# QuadDXL.net
KiCad netlist of a schematic drawn in EAGLE
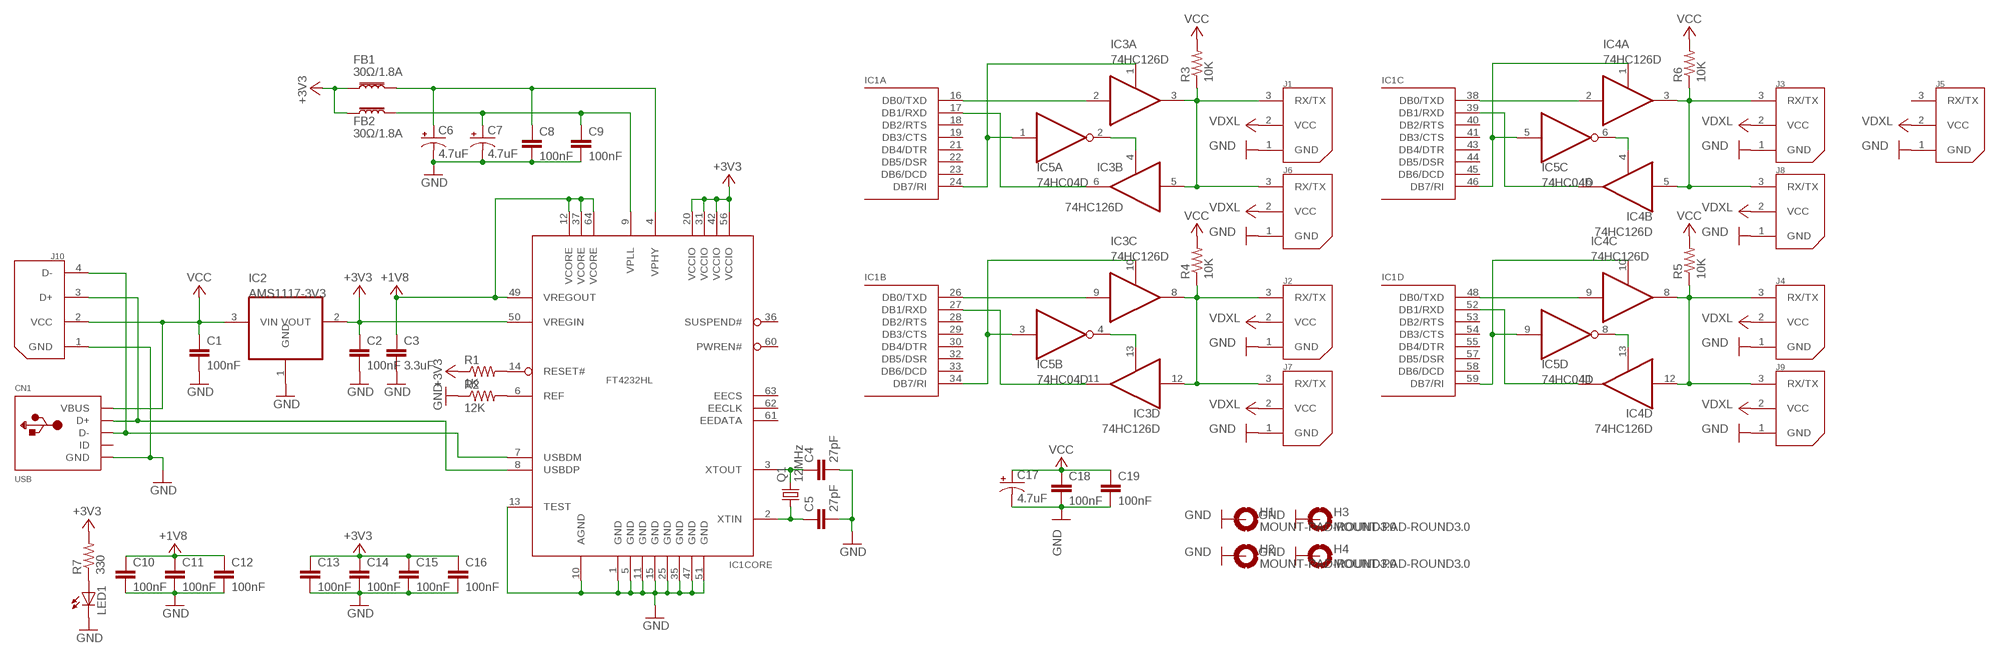
[diagram p0: schematic, sheet 1]

(export (version "E")
  (design (tool "Eeschema 10.0.6"))
  (components
    (comp (ref "C1")
      (value "100nF")
      (footprint "eagle-import:C0603K")
      (libsource (lib "eagle-import") (part "C-EUC0603K"))
    )
    (comp (ref "C2")
      (value "100nF")
      (footprint "eagle-import:C0603K")
      (libsource (lib "eagle-import") (part "C-EUC0603K"))
    )
    (comp (ref "C3")
      (value "3.3uF")
      (footprint "eagle-import:C0603K")
      (libsource (lib "eagle-import") (part "C-EUC0603K"))
    )
    (comp (ref "C4")
      (value "27pF")
      (footprint "eagle-import:C0603K")
      (libsource (lib "eagle-import") (part "C-EUC0603K"))
    )
    (comp (ref "C5")
      (value "27pF")
      (footprint "eagle-import:C0603K")
      (libsource (lib "eagle-import") (part "C-EUC0603K"))
    )
    (comp (ref "C6")
      (value "4.7uF")
      (footprint "eagle-import:CT3216")
      (libsource (lib "eagle-import") (part "CPOL-USCT3216"))
    )
    (comp (ref "C7")
      (value "4.7uF")
      (footprint "eagle-import:CT3216")
      (libsource (lib "eagle-import") (part "CPOL-USCT3216"))
    )
    (comp (ref "C8")
      (value "100nF")
      (footprint "eagle-import:C0603K")
      (libsource (lib "eagle-import") (part "C-EUC0603K"))
    )
    (comp (ref "C9")
      (value "100nF")
      (footprint "eagle-import:C0603K")
      (libsource (lib "eagle-import") (part "C-EUC0603K"))
    )
    (comp (ref "C10")
      (value "100nF")
      (footprint "eagle-import:C0603K")
      (libsource (lib "eagle-import") (part "C-EUC0603K"))
    )
    (comp (ref "C11")
      (value "100nF")
      (footprint "eagle-import:C0603K")
      (libsource (lib "eagle-import") (part "C-EUC0603K"))
    )
    (comp (ref "C12")
      (value "100nF")
      (footprint "eagle-import:C0603K")
      (libsource (lib "eagle-import") (part "C-EUC0603K"))
    )
    (comp (ref "C13")
      (value "100nF")
      (footprint "eagle-import:C0603K")
      (libsource (lib "eagle-import") (part "C-EUC0603K"))
    )
    (comp (ref "C14")
      (value "100nF")
      (footprint "eagle-import:C0603K")
      (libsource (lib "eagle-import") (part "C-EUC0603K"))
    )
    (comp (ref "C15")
      (value "100nF")
      (footprint "eagle-import:C0603K")
      (libsource (lib "eagle-import") (part "C-EUC0603K"))
    )
    (comp (ref "C16")
      (value "100nF")
      (footprint "eagle-import:C0603K")
      (libsource (lib "eagle-import") (part "C-EUC0603K"))
    )
    (comp (ref "C17")
      (value "4.7uF")
      (footprint "eagle-import:CT3216")
      (libsource (lib "eagle-import") (part "CPOL-USCT3216"))
    )
    (comp (ref "C18")
      (value "100nF")
      (footprint "eagle-import:C0603K")
      (libsource (lib "eagle-import") (part "C-EUC0603K"))
    )
    (comp (ref "C19")
      (value "100nF")
      (footprint "eagle-import:C0603K")
      (libsource (lib "eagle-import") (part "C-EUC0603K"))
    )
    (comp (ref "CN1")
      (value "USB")
      (footprint "eagle-import:USB-MINIB")
      (libsource (lib "eagle-import") (part "USBMINIB"))
    )
    (comp (ref "FB1")
      (value "30Ω/1.8A")
      (footprint "eagle-import:0603")
      (libsource (lib "eagle-import") (part "FERRITE_BEAD-0603"))
    )
    (comp (ref "FB2")
      (value "30Ω/1.8A")
      (footprint "eagle-import:0603")
      (libsource (lib "eagle-import") (part "FERRITE_BEAD-0603"))
    )
    (comp (ref "H1")
      (value "MOUNT-PAD-ROUND3.0")
      (footprint "eagle-import:3,0-PAD")
      (libsource (lib "eagle-import") (part "MOUNT-PAD-ROUND3.0"))
    )
    (comp (ref "H2")
      (value "MOUNT-PAD-ROUND3.0")
      (footprint "eagle-import:3,0-PAD")
      (libsource (lib "eagle-import") (part "MOUNT-PAD-ROUND3.0"))
    )
    (comp (ref "H3")
      (value "MOUNT-PAD-ROUND3.0")
      (footprint "eagle-import:3,0-PAD")
      (libsource (lib "eagle-import") (part "MOUNT-PAD-ROUND3.0"))
    )
    (comp (ref "H4")
      (value "MOUNT-PAD-ROUND3.0")
      (footprint "eagle-import:3,0-PAD")
      (libsource (lib "eagle-import") (part "MOUNT-PAD-ROUND3.0"))
    )
    (comp (ref "IC1")
      (value "FT4232HL")
      (footprint "eagle-import:LQFP64")
      (libsource (lib "eagle-import") (part "FT4232HL"))
    )
    (comp (ref "IC2")
      (value "AMS1117-3V3")
      (footprint "eagle-import:SOT223")
      (fields (field (name "MPN") "REG1117"))
      (libsource (lib "eagle-import") (part "REG1117"))
    )
    (comp (ref "IC3")
      (value "74HC126D")
      (footprint "eagle-import:SO14")
      (libsource (lib "eagle-import") (part "74126DHC"))
    )
    (comp (ref "IC4")
      (value "74HC126D")
      (footprint "eagle-import:SO14")
      (libsource (lib "eagle-import") (part "74126DHC"))
    )
    (comp (ref "IC5")
      (value "74HC04D")
      (footprint "eagle-import:SO14")
      (libsource (lib "eagle-import") (part "7404DHC"))
    )
    (comp (ref "J1")
      (value "22-03-5035")
      (footprint "eagle-import:5267-3")
      (libsource (lib "eagle-import") (part "22-03-5035"))
    )
    (comp (ref "J2")
      (value "22-03-5035")
      (footprint "eagle-import:5267-3")
      (libsource (lib "eagle-import") (part "22-03-5035"))
    )
    (comp (ref "J3")
      (value "22-03-5035")
      (footprint "eagle-import:5267-3")
      (libsource (lib "eagle-import") (part "22-03-5035"))
    )
    (comp (ref "J4")
      (value "22-03-5035")
      (footprint "eagle-import:5267-3")
      (libsource (lib "eagle-import") (part "22-03-5035"))
    )
    (comp (ref "J5")
      (value "DXL_POWER")
      (footprint "eagle-import:5267-3")
      (libsource (lib "eagle-import") (part "22-03-5035"))
    )
    (comp (ref "J6")
      (value "22-03-5035")
      (footprint "eagle-import:5267-3")
      (libsource (lib "eagle-import") (part "22-03-5035"))
    )
    (comp (ref "J7")
      (value "22-03-5035")
      (footprint "eagle-import:5267-3")
      (libsource (lib "eagle-import") (part "22-03-5035"))
    )
    (comp (ref "J8")
      (value "22-03-5035")
      (footprint "eagle-import:5267-3")
      (libsource (lib "eagle-import") (part "22-03-5035"))
    )
    (comp (ref "J9")
      (value "22-03-5035")
      (footprint "eagle-import:5267-3")
      (libsource (lib "eagle-import") (part "22-03-5035"))
    )
    (comp (ref "J10")
      (value "USB")
      (footprint "eagle-import:5267-4")
      (libsource (lib "eagle-import") (part "22-03-5045"))
    )
    (comp (ref "LED1")
      (value "LEDCHIP-LED0603")
      (footprint "eagle-import:CHIP-LED0603")
      (libsource (lib "eagle-import") (part "LEDCHIP-LED0603"))
    )
    (comp (ref "Q1")
      (value "12MHz")
      (footprint "eagle-import:HC49UP")
      (libsource (lib "eagle-import") (part "CRYSTALHC49UP"))
    )
    (comp (ref "R1")
      (value "1K")
      (footprint "eagle-import:R0603")
      (libsource (lib "eagle-import") (part "R-US_R0603"))
    )
    (comp (ref "R2")
      (value "12K")
      (footprint "eagle-import:R0603")
      (libsource (lib "eagle-import") (part "R-US_R0603"))
    )
    (comp (ref "R3")
      (value "10K")
      (footprint "eagle-import:R0603")
      (libsource (lib "eagle-import") (part "R-US_R0603"))
    )
    (comp (ref "R4")
      (value "10K")
      (footprint "eagle-import:R0603")
      (libsource (lib "eagle-import") (part "R-US_R0603"))
    )
    (comp (ref "R5")
      (value "10K")
      (footprint "eagle-import:R0603")
      (libsource (lib "eagle-import") (part "R-US_R0603"))
    )
    (comp (ref "R6")
      (value "10K")
      (footprint "eagle-import:R0603")
      (libsource (lib "eagle-import") (part "R-US_R0603"))
    )
    (comp (ref "R7")
      (value "330")
      (footprint "eagle-import:R0603")
      (libsource (lib "eagle-import") (part "R-US_R0603"))
    )
  )
  (nets
    (net (code "1") (name "+1V8") (class "Default")
      (node (ref "C10") (pin "1") (pinfunction "1_1") (pintype "passive"))
      (node (ref "C11") (pin "1") (pinfunction "1_1") (pintype "passive"))
      (node (ref "C12") (pin "1") (pinfunction "1_1") (pintype "passive"))
      (node (ref "C3") (pin "1") (pinfunction "1_1") (pintype "passive"))
      (node (ref "IC1") (pin "12") (pinfunction "VCORE_12") (pintype "power_in"))
      (node (ref "IC1") (pin "37") (pinfunction "VCORE_37") (pintype "power_in"))
      (node (ref "IC1") (pin "49") (pinfunction "VREGOUT_49") (pintype "output"))
      (node (ref "IC1") (pin "64") (pinfunction "VCORE_64") (pintype "power_in"))
    )
    (net (code "2") (name "+3V3") (class "Default")
      (node (ref "C13") (pin "1") (pinfunction "1_1") (pintype "passive"))
      (node (ref "C14") (pin "1") (pinfunction "1_1") (pintype "passive"))
      (node (ref "C15") (pin "1") (pinfunction "1_1") (pintype "passive"))
      (node (ref "C16") (pin "1") (pinfunction "1_1") (pintype "passive"))
      (node (ref "C2") (pin "1") (pinfunction "1_1") (pintype "passive"))
      (node (ref "FB1") (pin "1") (pinfunction "1_1") (pintype "passive"))
      (node (ref "FB2") (pin "1") (pinfunction "1_1") (pintype "passive"))
      (node (ref "IC1") (pin "20") (pinfunction "VCCIO_20") (pintype "power_in"))
      (node (ref "IC1") (pin "31") (pinfunction "VCCIO_31") (pintype "power_in"))
      (node (ref "IC1") (pin "42") (pinfunction "VCCIO_42") (pintype "power_in"))
      (node (ref "IC1") (pin "50") (pinfunction "VREGIN_50") (pintype "bidirectional"))
      (node (ref "IC1") (pin "56") (pinfunction "VCCIO_56") (pintype "power_in"))
      (node (ref "IC2") (pin "2") (pinfunction "VOUT_2") (pintype "output"))
      (node (ref "R1") (pin "1") (pinfunction "1_1") (pintype "passive"))
      (node (ref "R7") (pin "2") (pinfunction "2_2") (pintype "passive"))
    )
    (net (code "3") (name "GND") (class "Default")
      (node (ref "C1") (pin "2") (pinfunction "2_2") (pintype "passive"))
      (node (ref "C10") (pin "2") (pinfunction "2_2") (pintype "passive"))
      (node (ref "C11") (pin "2") (pinfunction "2_2") (pintype "passive"))
      (node (ref "C12") (pin "2") (pinfunction "2_2") (pintype "passive"))
      (node (ref "C13") (pin "2") (pinfunction "2_2") (pintype "passive"))
      (node (ref "C14") (pin "2") (pinfunction "2_2") (pintype "passive"))
      (node (ref "C15") (pin "2") (pinfunction "2_2") (pintype "passive"))
      (node (ref "C16") (pin "2") (pinfunction "2_2") (pintype "passive"))
      (node (ref "C17") (pin "-") (pinfunction "-_-") (pintype "passive"))
      (node (ref "C18") (pin "2") (pinfunction "2_2") (pintype "passive"))
      (node (ref "C19") (pin "2") (pinfunction "2_2") (pintype "passive"))
      (node (ref "C2") (pin "2") (pinfunction "2_2") (pintype "passive"))
      (node (ref "C3") (pin "2") (pinfunction "2_2") (pintype "passive"))
      (node (ref "C4") (pin "2") (pinfunction "2_2") (pintype "passive"))
      (node (ref "C5") (pin "2") (pinfunction "2_2") (pintype "passive"))
      (node (ref "C6") (pin "-") (pinfunction "-_-") (pintype "passive"))
      (node (ref "C7") (pin "-") (pinfunction "-_-") (pintype "passive"))
      (node (ref "C8") (pin "2") (pinfunction "2_2") (pintype "passive"))
      (node (ref "C9") (pin "2") (pinfunction "2_2") (pintype "passive"))
      (node (ref "CN1") (pin "GND") (pinfunction "GND_GND") (pintype "power_in"))
      (node (ref "H1") (pin "B3,0") (pinfunction "MOUNT_B3,0") (pintype "passive"))
      (node (ref "H2") (pin "B3,0") (pinfunction "MOUNT_B3,0") (pintype "passive"))
      (node (ref "H3") (pin "B3,0") (pinfunction "MOUNT_B3,0") (pintype "passive"))
      (node (ref "H4") (pin "B3,0") (pinfunction "MOUNT_B3,0") (pintype "passive"))
      (node (ref "IC1") (pin "1") (pinfunction "GND_1") (pintype "power_in"))
      (node (ref "IC1") (pin "10") (pinfunction "AGND_10") (pintype "power_in"))
      (node (ref "IC1") (pin "11") (pinfunction "GND_11") (pintype "power_in"))
      (node (ref "IC1") (pin "13") (pinfunction "TEST_13") (pintype "input"))
      (node (ref "IC1") (pin "15") (pinfunction "GND_15") (pintype "power_in"))
      (node (ref "IC1") (pin "25") (pinfunction "GND_25") (pintype "power_in"))
      (node (ref "IC1") (pin "35") (pinfunction "GND_35") (pintype "power_in"))
      (node (ref "IC1") (pin "47") (pinfunction "GND_47") (pintype "power_in"))
      (node (ref "IC1") (pin "5") (pinfunction "GND_5") (pintype "power_in"))
      (node (ref "IC1") (pin "51") (pinfunction "GND_51") (pintype "power_in"))
      (node (ref "IC2") (pin "1") (pinfunction "GND_1") (pintype "power_in"))
      (node (ref "J1") (pin "1") (pinfunction "GND_1") (pintype "bidirectional"))
      (node (ref "J10") (pin "1") (pinfunction "GND_1") (pintype "bidirectional"))
      (node (ref "J2") (pin "1") (pinfunction "GND_1") (pintype "bidirectional"))
      (node (ref "J3") (pin "1") (pinfunction "GND_1") (pintype "bidirectional"))
      (node (ref "J4") (pin "1") (pinfunction "GND_1") (pintype "bidirectional"))
      (node (ref "J5") (pin "1") (pinfunction "GND_1") (pintype "bidirectional"))
      (node (ref "J6") (pin "1") (pinfunction "GND_1") (pintype "bidirectional"))
      (node (ref "J7") (pin "1") (pinfunction "GND_1") (pintype "bidirectional"))
      (node (ref "J8") (pin "1") (pinfunction "GND_1") (pintype "bidirectional"))
      (node (ref "J9") (pin "1") (pinfunction "GND_1") (pintype "bidirectional"))
      (node (ref "LED1") (pin "C") (pinfunction "C_C") (pintype "passive"))
      (node (ref "R2") (pin "1") (pinfunction "1_1") (pintype "passive"))
    )
    (net (code "4") (name "Net-(IC1A-DB0{slash}TXD)") (class "Default")
      (node (ref "IC1") (pin "16") (pinfunction "DB0/TXD_16") (pintype "bidirectional"))
      (node (ref "IC3") (pin "2") (pinfunction "I_2") (pintype "input"))
    )
    (net (code "5") (name "Net-(IC1A-DB1{slash}RXD)") (class "Default")
      (node (ref "IC1") (pin "17") (pinfunction "DB1/RXD_17") (pintype "bidirectional"))
      (node (ref "IC3") (pin "6") (pinfunction "O_6") (pintype "output"))
    )
    (net (code "6") (name "Net-(IC1A-DB7{slash}RI)") (class "Default")
      (node (ref "IC1") (pin "24") (pinfunction "DB7/RI_24") (pintype "bidirectional"))
      (node (ref "IC3") (pin "1") (pinfunction "OE_1") (pintype "input"))
      (node (ref "IC5") (pin "1") (pinfunction "I_1") (pintype "input"))
    )
    (net (code "7") (name "Net-(IC1B-DB0{slash}TXD)") (class "Default")
      (node (ref "IC1") (pin "26") (pinfunction "DB0/TXD_26") (pintype "bidirectional"))
      (node (ref "IC3") (pin "9") (pinfunction "I_9") (pintype "input"))
    )
    (net (code "8") (name "Net-(IC1B-DB1{slash}RXD)") (class "Default")
      (node (ref "IC1") (pin "27") (pinfunction "DB1/RXD_27") (pintype "bidirectional"))
      (node (ref "IC3") (pin "11") (pinfunction "O_11") (pintype "output"))
    )
    (net (code "9") (name "Net-(IC1B-DB7{slash}RI)") (class "Default")
      (node (ref "IC1") (pin "34") (pinfunction "DB7/RI_34") (pintype "bidirectional"))
      (node (ref "IC3") (pin "10") (pinfunction "OE_10") (pintype "input"))
      (node (ref "IC5") (pin "3") (pinfunction "I_3") (pintype "input"))
    )
    (net (code "10") (name "Net-(IC1C-DB0{slash}TXD)") (class "Default")
      (node (ref "IC1") (pin "38") (pinfunction "DB0/TXD_38") (pintype "bidirectional"))
      (node (ref "IC4") (pin "2") (pinfunction "I_2") (pintype "input"))
    )
    (net (code "11") (name "Net-(IC1C-DB1{slash}RXD)") (class "Default")
      (node (ref "IC1") (pin "39") (pinfunction "DB1/RXD_39") (pintype "bidirectional"))
      (node (ref "IC4") (pin "6") (pinfunction "O_6") (pintype "output"))
    )
    (net (code "12") (name "Net-(IC1C-DB7{slash}RI)") (class "Default")
      (node (ref "IC1") (pin "46") (pinfunction "DB7/RI_46") (pintype "bidirectional"))
      (node (ref "IC4") (pin "1") (pinfunction "OE_1") (pintype "input"))
      (node (ref "IC5") (pin "5") (pinfunction "I_5") (pintype "input"))
    )
    (net (code "13") (name "Net-(IC1D-REF)") (class "Default")
      (node (ref "IC1") (pin "6") (pinfunction "REF_6") (pintype "input"))
      (node (ref "R2") (pin "2") (pinfunction "2_2") (pintype "passive"))
    )
    (net (code "14") (name "Net-(IC1D-RESET#)") (class "Default")
      (node (ref "IC1") (pin "14") (pinfunction "RESET#_14") (pintype "input"))
      (node (ref "R1") (pin "2") (pinfunction "2_2") (pintype "passive"))
    )
    (net (code "15") (name "Net-(IC1D-USBDM)") (class "Default")
      (node (ref "CN1") (pin "D-") (pinfunction "D-_D-") (pintype "bidirectional"))
      (node (ref "IC1") (pin "7") (pinfunction "USBDM_7") (pintype "input"))
      (node (ref "J10") (pin "4") (pinfunction "D-_4") (pintype "bidirectional"))
    )
    (net (code "16") (name "Net-(IC1D-USBDP)") (class "Default")
      (node (ref "CN1") (pin "D+") (pinfunction "D+_D+") (pintype "bidirectional"))
      (node (ref "IC1") (pin "8") (pinfunction "USBDP_8") (pintype "input"))
      (node (ref "J10") (pin "3") (pinfunction "D+_3") (pintype "bidirectional"))
    )
    (net (code "17") (name "Net-(IC1D-VPHY)") (class "Default")
      (node (ref "C6") (pin "+") (pinfunction "+_+") (pintype "passive"))
      (node (ref "C8") (pin "1") (pinfunction "1_1") (pintype "passive"))
      (node (ref "FB1") (pin "2") (pinfunction "2_2") (pintype "passive"))
      (node (ref "IC1") (pin "4") (pinfunction "VPHY_4") (pintype "power_in"))
    )
    (net (code "18") (name "Net-(IC1D-VPLL)") (class "Default")
      (node (ref "C7") (pin "+") (pinfunction "+_+") (pintype "passive"))
      (node (ref "C9") (pin "1") (pinfunction "1_1") (pintype "passive"))
      (node (ref "FB2") (pin "2") (pinfunction "2_2") (pintype "passive"))
      (node (ref "IC1") (pin "9") (pinfunction "VPLL_9") (pintype "power_in"))
    )
    (net (code "19") (name "Net-(IC1D-XTIN)") (class "Default")
      (node (ref "C5") (pin "1") (pinfunction "1_1") (pintype "passive"))
      (node (ref "IC1") (pin "2") (pinfunction "XTIN_2") (pintype "input"))
      (node (ref "Q1") (pin "1") (pinfunction "1_1") (pintype "passive"))
    )
    (net (code "20") (name "Net-(IC1D-XTOUT)") (class "Default")
      (node (ref "C4") (pin "1") (pinfunction "1_1") (pintype "passive"))
      (node (ref "IC1") (pin "3") (pinfunction "XTOUT_3") (pintype "output"))
      (node (ref "Q1") (pin "2") (pinfunction "2_2") (pintype "passive"))
    )
    (net (code "21") (name "Net-(IC1E-DB0{slash}TXD)") (class "Default")
      (node (ref "IC1") (pin "48") (pinfunction "DB0/TXD_48") (pintype "bidirectional"))
      (node (ref "IC4") (pin "9") (pinfunction "I_9") (pintype "input"))
    )
    (net (code "22") (name "Net-(IC1E-DB1{slash}RXD)") (class "Default")
      (node (ref "IC1") (pin "52") (pinfunction "DB1/RXD_52") (pintype "bidirectional"))
      (node (ref "IC4") (pin "11") (pinfunction "O_11") (pintype "output"))
    )
    (net (code "23") (name "Net-(IC1E-DB7{slash}RI)") (class "Default")
      (node (ref "IC1") (pin "59") (pinfunction "DB7/RI_59") (pintype "bidirectional"))
      (node (ref "IC4") (pin "10") (pinfunction "OE_10") (pintype "input"))
      (node (ref "IC5") (pin "9") (pinfunction "I_9") (pintype "input"))
    )
    (net (code "24") (name "Net-(IC3A-O)") (class "Default")
      (node (ref "IC3") (pin "3") (pinfunction "O_3") (pintype "output"))
      (node (ref "IC3") (pin "5") (pinfunction "I_5") (pintype "input"))
      (node (ref "J1") (pin "3") (pinfunction "RX/TX_3") (pintype "bidirectional"))
      (node (ref "J6") (pin "3") (pinfunction "RX/TX_3") (pintype "bidirectional"))
      (node (ref "R3") (pin "1") (pinfunction "1_1") (pintype "passive"))
    )
    (net (code "25") (name "Net-(IC3B-OE)") (class "Default")
      (node (ref "IC3") (pin "4") (pinfunction "OE_4") (pintype "input"))
      (node (ref "IC5") (pin "2") (pinfunction "O_2") (pintype "output"))
    )
    (net (code "26") (name "Net-(IC3C-O)") (class "Default")
      (node (ref "IC3") (pin "12") (pinfunction "I_12") (pintype "input"))
      (node (ref "IC3") (pin "8") (pinfunction "O_8") (pintype "output"))
      (node (ref "J2") (pin "3") (pinfunction "RX/TX_3") (pintype "bidirectional"))
      (node (ref "J7") (pin "3") (pinfunction "RX/TX_3") (pintype "bidirectional"))
      (node (ref "R4") (pin "1") (pinfunction "1_1") (pintype "passive"))
    )
    (net (code "27") (name "Net-(IC3D-OE)") (class "Default")
      (node (ref "IC3") (pin "13") (pinfunction "OE_13") (pintype "input"))
      (node (ref "IC5") (pin "4") (pinfunction "O_4") (pintype "output"))
    )
    (net (code "28") (name "Net-(IC4A-O)") (class "Default")
      (node (ref "IC4") (pin "3") (pinfunction "O_3") (pintype "output"))
      (node (ref "IC4") (pin "5") (pinfunction "I_5") (pintype "input"))
      (node (ref "J3") (pin "3") (pinfunction "RX/TX_3") (pintype "bidirectional"))
      (node (ref "J8") (pin "3") (pinfunction "RX/TX_3") (pintype "bidirectional"))
      (node (ref "R6") (pin "1") (pinfunction "1_1") (pintype "passive"))
    )
    (net (code "29") (name "Net-(IC4B-OE)") (class "Default")
      (node (ref "IC4") (pin "4") (pinfunction "OE_4") (pintype "input"))
      (node (ref "IC5") (pin "6") (pinfunction "O_6") (pintype "output"))
    )
    (net (code "30") (name "Net-(IC4C-O)") (class "Default")
      (node (ref "IC4") (pin "12") (pinfunction "I_12") (pintype "input"))
      (node (ref "IC4") (pin "8") (pinfunction "O_8") (pintype "output"))
      (node (ref "J4") (pin "3") (pinfunction "RX/TX_3") (pintype "bidirectional"))
      (node (ref "J9") (pin "3") (pinfunction "RX/TX_3") (pintype "bidirectional"))
      (node (ref "R5") (pin "1") (pinfunction "1_1") (pintype "passive"))
    )
    (net (code "31") (name "Net-(IC4D-OE)") (class "Default")
      (node (ref "IC4") (pin "13") (pinfunction "OE_13") (pintype "input"))
      (node (ref "IC5") (pin "8") (pinfunction "O_8") (pintype "output"))
    )
    (net (code "32") (name "Net-(LED1-PadA)") (class "Default")
      (node (ref "LED1") (pin "A") (pinfunction "A_A") (pintype "passive"))
      (node (ref "R7") (pin "1") (pinfunction "1_1") (pintype "passive"))
    )
    (net (code "33") (name "VCC") (class "Default")
      (node (ref "C1") (pin "1") (pinfunction "1_1") (pintype "passive"))
      (node (ref "C17") (pin "+") (pinfunction "+_+") (pintype "passive"))
      (node (ref "C18") (pin "1") (pinfunction "1_1") (pintype "passive"))
      (node (ref "C19") (pin "1") (pinfunction "1_1") (pintype "passive"))
      (node (ref "CN1") (pin "VBUS") (pinfunction "VBUS_VBUS") (pintype "power_in"))
      (node (ref "IC2") (pin "3") (pinfunction "VIN_3") (pintype "input"))
      (node (ref "J10") (pin "2") (pinfunction "VCC_2") (pintype "bidirectional"))
      (node (ref "R3") (pin "2") (pinfunction "2_2") (pintype "passive"))
      (node (ref "R4") (pin "2") (pinfunction "2_2") (pintype "passive"))
      (node (ref "R5") (pin "2") (pinfunction "2_2") (pintype "passive"))
      (node (ref "R6") (pin "2") (pinfunction "2_2") (pintype "passive"))
    )
    (net (code "34") (name "VDXL") (class "Default")
      (node (ref "J1") (pin "2") (pinfunction "VCC_2") (pintype "bidirectional"))
      (node (ref "J2") (pin "2") (pinfunction "VCC_2") (pintype "bidirectional"))
      (node (ref "J3") (pin "2") (pinfunction "VCC_2") (pintype "bidirectional"))
      (node (ref "J4") (pin "2") (pinfunction "VCC_2") (pintype "bidirectional"))
      (node (ref "J5") (pin "2") (pinfunction "VCC_2") (pintype "bidirectional"))
      (node (ref "J6") (pin "2") (pinfunction "VCC_2") (pintype "bidirectional"))
      (node (ref "J7") (pin "2") (pinfunction "VCC_2") (pintype "bidirectional"))
      (node (ref "J8") (pin "2") (pinfunction "VCC_2") (pintype "bidirectional"))
      (node (ref "J9") (pin "2") (pinfunction "VCC_2") (pintype "bidirectional"))
    )
    (net (code "35") (name "unconnected-(CN1-PadID)") (class "Default")
      (node (ref "CN1") (pin "ID") (pinfunction "ID_ID") (pintype "bidirectional"))
    )
    (net (code "36") (name "unconnected-(IC1A-DB2{slash}RTS-Pad18)") (class "Default")
      (node (ref "IC1") (pin "18") (pinfunction "DB2/RTS_18") (pintype "bidirectional"))
    )
    (net (code "37") (name "unconnected-(IC1A-DB3{slash}CTS-Pad19)") (class "Default")
      (node (ref "IC1") (pin "19") (pinfunction "DB3/CTS_19") (pintype "bidirectional"))
    )
    (net (code "38") (name "unconnected-(IC1A-DB4{slash}DTR-Pad21)") (class "Default")
      (node (ref "IC1") (pin "21") (pinfunction "DB4/DTR_21") (pintype "bidirectional"))
    )
    (net (code "39") (name "unconnected-(IC1A-DB5{slash}DSR-Pad22)") (class "Default")
      (node (ref "IC1") (pin "22") (pinfunction "DB5/DSR_22") (pintype "bidirectional"))
    )
    (net (code "40") (name "unconnected-(IC1A-DB6{slash}DCD-Pad23)") (class "Default")
      (node (ref "IC1") (pin "23") (pinfunction "DB6/DCD_23") (pintype "bidirectional"))
    )
    (net (code "41") (name "unconnected-(IC1B-DB2{slash}RTS-Pad28)") (class "Default")
      (node (ref "IC1") (pin "28") (pinfunction "DB2/RTS_28") (pintype "bidirectional"))
    )
    (net (code "42") (name "unconnected-(IC1B-DB3{slash}CTS-Pad29)") (class "Default")
      (node (ref "IC1") (pin "29") (pinfunction "DB3/CTS_29") (pintype "bidirectional"))
    )
    (net (code "43") (name "unconnected-(IC1B-DB4{slash}DTR-Pad30)") (class "Default")
      (node (ref "IC1") (pin "30") (pinfunction "DB4/DTR_30") (pintype "bidirectional"))
    )
    (net (code "44") (name "unconnected-(IC1B-DB5{slash}DSR-Pad32)") (class "Default")
      (node (ref "IC1") (pin "32") (pinfunction "DB5/DSR_32") (pintype "bidirectional"))
    )
    (net (code "45") (name "unconnected-(IC1B-DB6{slash}DCD-Pad33)") (class "Default")
      (node (ref "IC1") (pin "33") (pinfunction "DB6/DCD_33") (pintype "bidirectional"))
    )
    (net (code "46") (name "unconnected-(IC1C-DB2{slash}RTS-Pad40)") (class "Default")
      (node (ref "IC1") (pin "40") (pinfunction "DB2/RTS_40") (pintype "bidirectional"))
    )
    (net (code "47") (name "unconnected-(IC1C-DB3{slash}CTS-Pad41)") (class "Default")
      (node (ref "IC1") (pin "41") (pinfunction "DB3/CTS_41") (pintype "bidirectional"))
    )
    (net (code "48") (name "unconnected-(IC1C-DB4{slash}DTR-Pad43)") (class "Default")
      (node (ref "IC1") (pin "43") (pinfunction "DB4/DTR_43") (pintype "bidirectional"))
    )
    (net (code "49") (name "unconnected-(IC1C-DB5{slash}DSR-Pad44)") (class "Default")
      (node (ref "IC1") (pin "44") (pinfunction "DB5/DSR_44") (pintype "bidirectional"))
    )
    (net (code "50") (name "unconnected-(IC1C-DB6{slash}DCD-Pad45)") (class "Default")
      (node (ref "IC1") (pin "45") (pinfunction "DB6/DCD_45") (pintype "bidirectional"))
    )
    (net (code "51") (name "unconnected-(IC1D-EECLK-Pad62)") (class "Default")
      (node (ref "IC1") (pin "62") (pinfunction "EECLK_62") (pintype "output"))
    )
    (net (code "52") (name "unconnected-(IC1D-EECS-Pad63)") (class "Default")
      (node (ref "IC1") (pin "63") (pinfunction "EECS_63") (pintype "bidirectional"))
    )
    (net (code "53") (name "unconnected-(IC1D-EEDATA-Pad61)") (class "Default")
      (node (ref "IC1") (pin "61") (pinfunction "EEDATA_61") (pintype "bidirectional"))
    )
    (net (code "54") (name "unconnected-(IC1D-PWREN#-Pad60)") (class "Default")
      (node (ref "IC1") (pin "60") (pinfunction "PWREN#_60") (pintype "output"))
    )
    (net (code "55") (name "unconnected-(IC1D-SUSPEND#-Pad36)") (class "Default")
      (node (ref "IC1") (pin "36") (pinfunction "SUSPEND#_36") (pintype "output"))
    )
    (net (code "56") (name "unconnected-(IC1E-DB2{slash}RTS-Pad53)") (class "Default")
      (node (ref "IC1") (pin "53") (pinfunction "DB2/RTS_53") (pintype "bidirectional"))
    )
    (net (code "57") (name "unconnected-(IC1E-DB3{slash}CTS-Pad54)") (class "Default")
      (node (ref "IC1") (pin "54") (pinfunction "DB3/CTS_54") (pintype "bidirectional"))
    )
    (net (code "58") (name "unconnected-(IC1E-DB4{slash}DTR-Pad55)") (class "Default")
      (node (ref "IC1") (pin "55") (pinfunction "DB4/DTR_55") (pintype "bidirectional"))
    )
    (net (code "59") (name "unconnected-(IC1E-DB5{slash}DSR-Pad57)") (class "Default")
      (node (ref "IC1") (pin "57") (pinfunction "DB5/DSR_57") (pintype "bidirectional"))
    )
    (net (code "60") (name "unconnected-(IC1E-DB6{slash}DCD-Pad58)") (class "Default")
      (node (ref "IC1") (pin "58") (pinfunction "DB6/DCD_58") (pintype "bidirectional"))
    )
    (net (code "61") (name "unconnected-(J5-RX{slash}TX-Pad3)") (class "Default")
      (node (ref "J5") (pin "3") (pinfunction "RX/TX_3") (pintype "bidirectional"))
    )
  )
)
